# Aux_MCU_ATmega16U4.net
KiCad netlist of a schematic drawn in Altium Designer
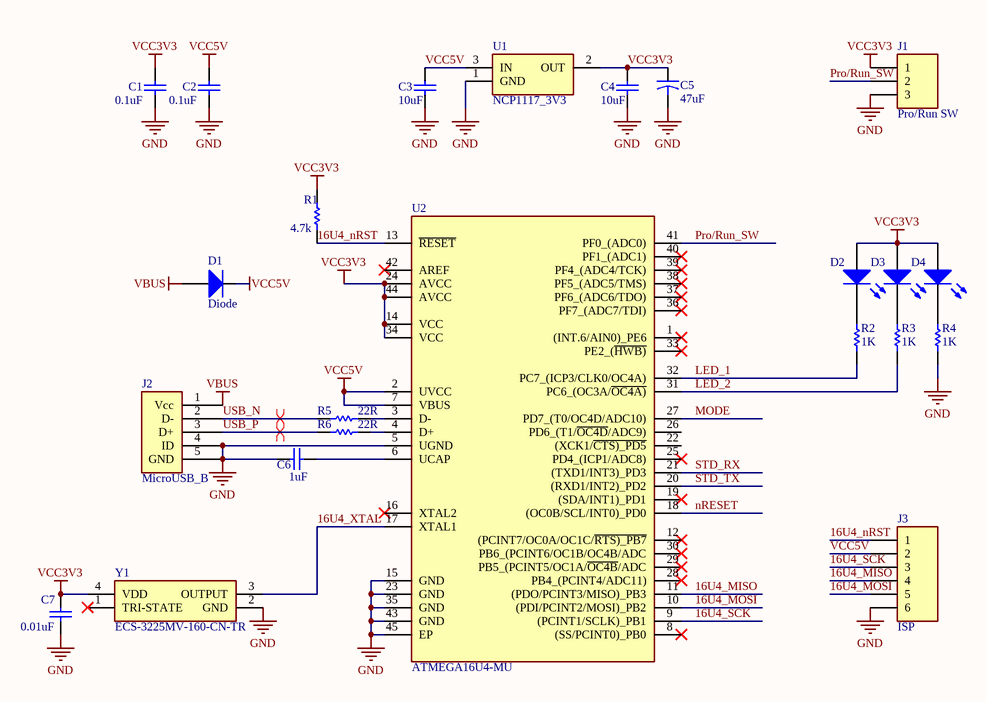
[diagram p0: Aux_MCU_ATmega16U4.SchDoc]

(export (version "E")
  (design (tool "Eeschema 10.0.6"))
  (components
    (comp (ref "C1")
      (value "0.1uF")
      (footprint "SMD0603")
      (description "Capacitor (Semiconductor SIM Model)")
      (fields (field (name "PUBLISHER") "Altium Limited"))
      (libsource (lib "Miscellaneous Devices") (part "Cap Semi"))
    )
    (comp (ref "C2")
      (value "0.1uF")
      (footprint "SMD0603")
      (description "Capacitor (Semiconductor SIM Model)")
      (fields (field (name "PUBLISHER") "Altium Limited"))
      (libsource (lib "Miscellaneous Devices") (part "Cap Semi"))
    )
    (comp (ref "C3")
      (value "10uF")
      (footprint "SMD0603")
      (description "Capacitor (Semiconductor SIM Model)")
      (fields (field (name "PUBLISHER") "Altium Limited"))
      (libsource (lib "Miscellaneous Devices") (part "Cap Semi"))
    )
    (comp (ref "C4")
      (value "10uF")
      (footprint "SMD0603")
      (description "Capacitor (Semiconductor SIM Model)")
      (fields (field (name "PUBLISHER") "Altium Limited"))
      (libsource (lib "Miscellaneous Devices") (part "Cap Semi"))
    )
    (comp (ref "C5")
      (value "47uF")
      (footprint "TAJ_CLASS_C")
      (description "Capacitor")
      (fields (field (name "PUBLISHER") "Altium Limited"))
      (libsource (lib "SRV8") (part "Cap2"))
    )
    (comp (ref "C6")
      (value "1uF")
      (footprint "SMD0603")
      (description "Capacitor (Semiconductor SIM Model)")
      (fields (field (name "PUBLISHER") "Altium Limited"))
      (libsource (lib "Miscellaneous Devices") (part "Cap Semi"))
    )
    (comp (ref "C7")
      (value "0.01uF")
      (footprint "SMD0603")
      (description "Capacitor (Semiconductor SIM Model)")
      (fields (field (name "PUBLISHER") "Altium Limited"))
      (libsource (lib "Miscellaneous Devices") (part "Cap Semi"))
    )
    (comp (ref "D1")
      (value "Diode")
      (footprint "SMB_DIODE_B130LB")
      (description "Default Diode")
      (fields (field (name "PUBLISHER") "Altium Limited"))
      (libsource (lib "Miscellaneous Devices") (part "Diode"))
    )
    (comp (ref "D2")
      (value "LED0")
      (footprint "SMD0603_LED")
      (description "Typical INFRARED GaAs LED")
      (fields (field (name "PUBLISHER") "Altium Limited"))
      (libsource (lib "Miscellaneous Devices") (part "LED0"))
    )
    (comp (ref "D3")
      (value "LED0")
      (footprint "SMD0603_LED")
      (description "Typical INFRARED GaAs LED")
      (fields (field (name "PUBLISHER") "Altium Limited"))
      (libsource (lib "Miscellaneous Devices") (part "LED0"))
    )
    (comp (ref "D4")
      (value "LED0")
      (footprint "SMD0603_LED")
      (description "Typical INFRARED GaAs LED")
      (fields (field (name "PUBLISHER") "Altium Limited"))
      (libsource (lib "Miscellaneous Devices") (part "LED0"))
    )
    (comp (ref "J1")
      (value "Pro/Run SW")
      (footprint "SLIDE_SW_3P")
      (description "Program/Run Switch")
      (libsource (lib "ATSAME54p20a_Ethernet") (part "Pro/Run SW"))
    )
    (comp (ref "J2")
      (value "MicroUSB_B")
      (footprint "micro_usb_molex_105017-0001")
      (libsource (lib "ATSAME54p20a_Ethernet") (part "MicroUSB_B"))
    )
    (comp (ref "J3") (value "ISP") (footprint "ISP") (libsource (lib "ATSAME54p20a_Ethernet") (part "ISP")))
    (comp (ref "R1")
      (value "4.7k")
      (footprint "SMD0603")
      (description "Semiconductor Resistor")
      (fields (field (name "Comment") "4.7K"))
      (libsource (lib "*") (part "Res"))
    )
    (comp (ref "R2")
      (value "1K")
      (footprint "SMD0603")
      (description "Semiconductor Resistor")
      (fields (field (name "PUBLISHER") "Altium Limited"))
      (libsource (lib "Miscellaneous Devices") (part "Res Semi"))
    )
    (comp (ref "R3")
      (value "1K")
      (footprint "SMD0603")
      (description "Semiconductor Resistor")
      (fields (field (name "PUBLISHER") "Altium Limited"))
      (libsource (lib "Miscellaneous Devices") (part "Res Semi"))
    )
    (comp (ref "R4")
      (value "1K")
      (footprint "SMD0603")
      (description "Semiconductor Resistor")
      (fields (field (name "PUBLISHER") "Altium Limited"))
      (libsource (lib "Miscellaneous Devices") (part "Res Semi"))
    )
    (comp (ref "R5")
      (value "22R")
      (footprint "SMD0603")
      (description "Semiconductor Resistor")
      (libsource (lib "*") (part "Res"))
    )
    (comp (ref "R6")
      (value "22R")
      (footprint "SMD0603")
      (description "Semiconductor Resistor")
      (libsource (lib "*") (part "Res"))
    )
    (comp (ref "U1")
      (value "NCP1117_3V3")
      (footprint "SOT-223-2")
      (description "IC REG 3.3V 1A DPAC")
      (libsource (lib "ATSAME54p20a_Ethernet") (part "NCP1117_3V3"))
    )
    (comp (ref "U2")
      (value "ATMEGA16U4-MU")
      (footprint "ATSAME54p20a_Ethernet:QFN50P700X700X100-45N-D")
      (description "Integrated Circuit")
      (libsource (lib "ATSAME54p20a_Ethernet") (part "ATMEGA16U4-MU"))
    )
    (comp (ref "Y1")
      (value "ECS-3225MV-160-CN-TR")
      (footprint "OSC3225")
      (description "Crystal or Oscillator")
      (fields (field (name "MOUSER2 PART NUMBER") "520-3225MV-160-CNT"))
      (libsource (lib "ATSAME54p20a_Ethernet") (part "ECS-3225MV-160-CN-TR"))
    )
  )
  (nets
    (net (code "1") (name "/16U4_MISO") (class "Default")
      (node (ref "J3") (pin "4") (pinfunction "4_4") (pintype "passive"))
      (node (ref "U2") (pin "11") (pinfunction "(PDO/PCINT3/MISO)_PB3_11") (pintype "passive"))
    )
    (net (code "2") (name "/16U4_MOSI") (class "Default")
      (node (ref "J3") (pin "5") (pinfunction "5_5") (pintype "passive"))
      (node (ref "U2") (pin "10") (pinfunction "(PDI/PCINT2/MOSI)_PB2_10") (pintype "passive"))
    )
    (net (code "3") (name "/16U4_SCK") (class "Default")
      (node (ref "J3") (pin "3") (pinfunction "3_3") (pintype "passive"))
      (node (ref "U2") (pin "9") (pinfunction "(PCINT1/SCLK)_PB1_9") (pintype "passive"))
    )
    (net (code "4") (name "/16U4_XTAL") (class "Default")
      (node (ref "U2") (pin "17") (pinfunction "XTAL1_17") (pintype "passive"))
      (node (ref "Y1") (pin "3") (pinfunction "OUTPUT_3") (pintype "passive"))
    )
    (net (code "5") (name "/16U4_nRST") (class "Default")
      (node (ref "J3") (pin "1") (pinfunction "1_1") (pintype "passive"))
      (node (ref "R1") (pin "1") (pinfunction "1_1") (pintype "passive"))
      (node (ref "U2") (pin "13") (pinfunction "~{RESET}_13") (pintype "passive"))
    )
    (net (code "6") (name "/LED_1") (class "Default")
      (node (ref "R2") (pin "1") (pinfunction "1_1") (pintype "passive"))
      (node (ref "U2") (pin "32") (pinfunction "PC7_(ICP3/CLK0/OC4A)_32") (pintype "passive"))
    )
    (net (code "7") (name "/LED_2") (class "Default")
      (node (ref "R3") (pin "1") (pinfunction "1_1") (pintype "passive"))
      (node (ref "U2") (pin "31") (pinfunction "PC6_(OC3A/~{OC4A)}_31") (pintype "passive"))
    )
    (net (code "8") (name "/MODE") (class "Default")
      (node (ref "U2") (pin "27") (pinfunction "PD7_(T0/OC4D/ADC10)_27") (pintype "passive"))
    )
    (net (code "9") (name "/Pro{slash}Run_SW") (class "Default")
      (node (ref "J1") (pin "2") (pinfunction "2_2") (pintype "passive"))
      (node (ref "U2") (pin "41") (pinfunction "PF0_(ADC0)_41") (pintype "passive"))
    )
    (net (code "10") (name "/STD_RX") (class "Default")
      (node (ref "U2") (pin "21") (pinfunction "(TXD1/INT3)_PD3_21") (pintype "passive"))
    )
    (net (code "11") (name "/STD_TX") (class "Default")
      (node (ref "U2") (pin "20") (pinfunction "(RXD1/INT2)_PD2_20") (pintype "passive"))
    )
    (net (code "12") (name "/USB_N") (class "Default")
      (node (ref "J2") (pin "2") (pinfunction "D-_2") (pintype "passive"))
      (node (ref "R5") (pin "2") (pinfunction "2_2") (pintype "passive"))
    )
    (net (code "13") (name "/USB_P") (class "Default")
      (node (ref "J2") (pin "3") (pinfunction "D+_3") (pintype "passive"))
      (node (ref "R6") (pin "2") (pinfunction "2_2") (pintype "passive"))
    )
    (net (code "14") (name "/nRESET") (class "Default")
      (node (ref "U2") (pin "18") (pinfunction "(OC0B/SCL/INT0)_PD0_18") (pintype "passive"))
    )
    (net (code "15") (name "GND") (class "Default")
      (node (ref "C1") (pin "2") (pinfunction "2_2") (pintype "passive"))
      (node (ref "C2") (pin "2") (pinfunction "2_2") (pintype "passive"))
      (node (ref "C3") (pin "1") (pinfunction "1_1") (pintype "passive"))
      (node (ref "C4") (pin "1") (pinfunction "1_1") (pintype "passive"))
      (node (ref "C5") (pin "2") (pinfunction "2_2") (pintype "passive"))
      (node (ref "C6") (pin "1") (pinfunction "1_1") (pintype "passive"))
      (node (ref "C7") (pin "1") (pinfunction "1_1") (pintype "passive"))
      (node (ref "J1") (pin "3") (pinfunction "3_3") (pintype "passive"))
      (node (ref "J2") (pin "4") (pinfunction "ID_4") (pintype "passive"))
      (node (ref "J2") (pin "5") (pinfunction "GND_5") (pintype "passive"))
      (node (ref "J3") (pin "6") (pinfunction "6_6") (pintype "passive"))
      (node (ref "R4") (pin "1") (pinfunction "1_1") (pintype "passive"))
      (node (ref "U1") (pin "1") (pinfunction "GND_1") (pintype "passive"))
      (node (ref "U2") (pin "15") (pinfunction "GND_15") (pintype "passive"))
      (node (ref "U2") (pin "23") (pinfunction "GND_23") (pintype "passive"))
      (node (ref "U2") (pin "35") (pinfunction "GND_35") (pintype "passive"))
      (node (ref "U2") (pin "43") (pinfunction "GND_43") (pintype "passive"))
      (node (ref "U2") (pin "45") (pinfunction "EP_45") (pintype "passive"))
      (node (ref "U2") (pin "5") (pinfunction "UGND_5") (pintype "passive"))
      (node (ref "Y1") (pin "2") (pinfunction "GND_2") (pintype "passive"))
    )
    (net (code "16") (name "Net-(D2-K)") (class "Default")
      (node (ref "D2") (pin "2") (pinfunction "K_2") (pintype "passive"))
      (node (ref "R2") (pin "2") (pinfunction "2_2") (pintype "passive"))
    )
    (net (code "17") (name "Net-(D3-K)") (class "Default")
      (node (ref "D3") (pin "2") (pinfunction "K_2") (pintype "passive"))
      (node (ref "R3") (pin "2") (pinfunction "2_2") (pintype "passive"))
    )
    (net (code "18") (name "Net-(D4-K)") (class "Default")
      (node (ref "D4") (pin "2") (pinfunction "K_2") (pintype "passive"))
      (node (ref "R4") (pin "2") (pinfunction "2_2") (pintype "passive"))
    )
    (net (code "19") (name "Net-(U2-D+)") (class "Default")
      (node (ref "R6") (pin "1") (pinfunction "1_1") (pintype "passive"))
      (node (ref "U2") (pin "4") (pinfunction "D+_4") (pintype "passive"))
    )
    (net (code "20") (name "Net-(U2-D-)") (class "Default")
      (node (ref "R5") (pin "1") (pinfunction "1_1") (pintype "passive"))
      (node (ref "U2") (pin "3") (pinfunction "D-_3") (pintype "passive"))
    )
    (net (code "21") (name "Net-(U2-UCAP)") (class "Default")
      (node (ref "C6") (pin "2") (pinfunction "2_2") (pintype "passive"))
      (node (ref "U2") (pin "6") (pinfunction "UCAP_6") (pintype "passive"))
    )
    (net (code "22") (name "VBUS") (class "Default")
      (node (ref "D1") (pin "1") (pinfunction "A_1") (pintype "passive"))
      (node (ref "J2") (pin "1") (pinfunction "Vcc_1") (pintype "passive"))
    )
    (net (code "23") (name "VCC3V3") (class "Default")
      (node (ref "C1") (pin "1") (pinfunction "1_1") (pintype "passive"))
      (node (ref "C4") (pin "2") (pinfunction "2_2") (pintype "passive"))
      (node (ref "C5") (pin "1") (pinfunction "1_1") (pintype "passive"))
      (node (ref "C7") (pin "2") (pinfunction "2_2") (pintype "passive"))
      (node (ref "D2") (pin "1") (pinfunction "A_1") (pintype "passive"))
      (node (ref "D3") (pin "1") (pinfunction "A_1") (pintype "passive"))
      (node (ref "D4") (pin "1") (pinfunction "A_1") (pintype "passive"))
      (node (ref "J1") (pin "1") (pinfunction "1_1") (pintype "passive"))
      (node (ref "R1") (pin "2") (pinfunction "2_2") (pintype "passive"))
      (node (ref "U1") (pin "2") (pinfunction "OUT_2") (pintype "passive"))
      (node (ref "U2") (pin "14") (pinfunction "VCC_14") (pintype "passive"))
      (node (ref "U2") (pin "24") (pinfunction "AVCC_24") (pintype "passive"))
      (node (ref "U2") (pin "34") (pinfunction "VCC_34") (pintype "passive"))
      (node (ref "U2") (pin "44") (pinfunction "AVCC_44") (pintype "passive"))
      (node (ref "Y1") (pin "4") (pinfunction "VDD_4") (pintype "passive"))
    )
    (net (code "24") (name "VCC5V") (class "Default")
      (node (ref "C2") (pin "1") (pinfunction "1_1") (pintype "passive"))
      (node (ref "C3") (pin "2") (pinfunction "2_2") (pintype "passive"))
      (node (ref "D1") (pin "2") (pinfunction "K_2") (pintype "passive"))
      (node (ref "J3") (pin "2") (pinfunction "2_2") (pintype "passive"))
      (node (ref "U1") (pin "3") (pinfunction "IN_3") (pintype "passive"))
      (node (ref "U2") (pin "2") (pinfunction "UVCC_2") (pintype "passive"))
      (node (ref "U2") (pin "7") (pinfunction "VBUS_7") (pintype "passive"))
    )
    (net (code "25") (name "unconnected-(U2-(INT.6{slash}AIN0)_PE6-Pad1)") (class "Default")
      (node (ref "U2") (pin "1") (pinfunction "(INT.6/AIN0)_PE6_1") (pintype "passive+no_connect"))
    )
    (net (code "26") (name "unconnected-(U2-(PCINT7{slash}OC0A{slash}OC1C{slash}~{RTS)_PB7}-Pad12)") (class "Default")
      (node (ref "U2") (pin "12") (pinfunction "(PCINT7/OC0A/OC1C/~{RTS)_PB7}_12") (pintype "passive+no_connect"))
    )
    (net (code "27") (name "unconnected-(U2-(SDA{slash}INT1)_PD1-Pad19)") (class "Default")
      (node (ref "U2") (pin "19") (pinfunction "(SDA/INT1)_PD1_19") (pintype "passive+no_connect"))
    )
    (net (code "28") (name "unconnected-(U2-(SS{slash}PCINT0)_PB0-Pad8)") (class "Default")
      (node (ref "U2") (pin "8") (pinfunction "(SS/PCINT0)_PB0_8") (pintype "passive+no_connect"))
    )
    (net (code "29") (name "unconnected-(U2-(XCK1{slash}~{CTS)_PD5}-Pad22)") (class "Default")
      (node (ref "U2") (pin "22") (pinfunction "(XCK1/~{CTS)_PD5}_22") (pintype "passive"))
    )
    (net (code "30") (name "unconnected-(U2-AREF-Pad42)") (class "Default")
      (node (ref "U2") (pin "42") (pinfunction "AREF_42") (pintype "passive+no_connect"))
    )
    (net (code "31") (name "unconnected-(U2-PB4_(PCINT4{slash}ADC11)-Pad28)") (class "Default")
      (node (ref "U2") (pin "28") (pinfunction "PB4_(PCINT4/ADC11)_28") (pintype "passive+no_connect"))
    )
    (net (code "32") (name "unconnected-(U2-PB5_(PCINT5{slash}OC1A{slash}~{OC4B}{slash}ADC-Pad29)") (class "Default")
      (node (ref "U2") (pin "29") (pinfunction "PB5_(PCINT5/OC1A/~{OC4B}/ADC_29") (pintype "passive+no_connect"))
    )
    (net (code "33") (name "unconnected-(U2-PB6_(PCINT6{slash}OC1B{slash}OC4B{slash}ADC-Pad30)") (class "Default")
      (node (ref "U2") (pin "30") (pinfunction "PB6_(PCINT6/OC1B/OC4B/ADC_30") (pintype "passive+no_connect"))
    )
    (net (code "34") (name "unconnected-(U2-PD4_(ICP1{slash}ADC8)-Pad25)") (class "Default")
      (node (ref "U2") (pin "25") (pinfunction "PD4_(ICP1/ADC8)_25") (pintype "passive+no_connect"))
    )
    (net (code "35") (name "unconnected-(U2-PD6_(T1{slash}~{OC4D}{slash}ADC9)-Pad26)") (class "Default")
      (node (ref "U2") (pin "26") (pinfunction "PD6_(T1/~{OC4D}/ADC9)_26") (pintype "passive"))
    )
    (net (code "36") (name "unconnected-(U2-PE2_(~{HWB)}-Pad33)") (class "Default")
      (node (ref "U2") (pin "33") (pinfunction "PE2_(~{HWB)}_33") (pintype "passive+no_connect"))
    )
    (net (code "37") (name "unconnected-(U2-PF1_(ADC1)-Pad40)") (class "Default")
      (node (ref "U2") (pin "40") (pinfunction "PF1_(ADC1)_40") (pintype "passive+no_connect"))
    )
    (net (code "38") (name "unconnected-(U2-PF4_(ADC4{slash}TCK)-Pad39)") (class "Default")
      (node (ref "U2") (pin "39") (pinfunction "PF4_(ADC4/TCK)_39") (pintype "passive+no_connect"))
    )
    (net (code "39") (name "unconnected-(U2-PF5_(ADC5{slash}TMS)-Pad38)") (class "Default")
      (node (ref "U2") (pin "38") (pinfunction "PF5_(ADC5/TMS)_38") (pintype "passive+no_connect"))
    )
    (net (code "40") (name "unconnected-(U2-PF6_(ADC6{slash}TDO)-Pad37)") (class "Default")
      (node (ref "U2") (pin "37") (pinfunction "PF6_(ADC6/TDO)_37") (pintype "passive+no_connect"))
    )
    (net (code "41") (name "unconnected-(U2-PF7_(ADC7{slash}TDI)-Pad36)") (class "Default")
      (node (ref "U2") (pin "36") (pinfunction "PF7_(ADC7/TDI)_36") (pintype "passive+no_connect"))
    )
    (net (code "42") (name "unconnected-(U2-XTAL2-Pad16)") (class "Default")
      (node (ref "U2") (pin "16") (pinfunction "XTAL2_16") (pintype "passive+no_connect"))
    )
    (net (code "43") (name "unconnected-(Y1-TRI-STATE-Pad1)") (class "Default")
      (node (ref "Y1") (pin "1") (pinfunction "TRI-STATE_1") (pintype "passive+no_connect"))
    )
  )
)
